# raspi_gpio_coupler.net
KiCad netlist of a schematic drawn in EAGLE
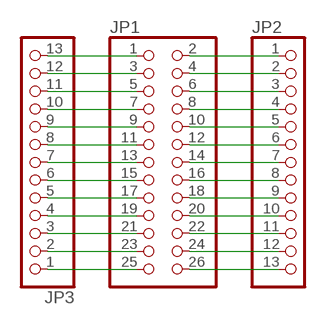
[diagram p0: schematic, sheet 1]

(export (version "E")
  (design (tool "Eeschema 10.0.6"))
  (components
    (comp (ref "JP1")
      (value "PINHD-2X13")
      (footprint "eagle-import:2X13")
      (libsource (lib "eagle-import") (part "PINHD-2X13"))
    )
    (comp (ref "JP2")
      (value "PINHD-1X13")
      (footprint "eagle-import:1X13")
      (libsource (lib "eagle-import") (part "PINHD-1X13"))
    )
    (comp (ref "JP3")
      (value "PINHD-1X13")
      (footprint "eagle-import:1X13")
      (libsource (lib "eagle-import") (part "PINHD-1X13"))
    )
  )
  (nets
    (net (code "1") (name "Net-(JP1-Pad1)") (class "Default")
      (node (ref "JP1") (pin "1") (pinfunction "1_1") (pintype "passive"))
      (node (ref "JP3") (pin "13") (pinfunction "13_13") (pintype "passive"))
    )
    (net (code "2") (name "Net-(JP1-Pad2)") (class "Default")
      (node (ref "JP1") (pin "2") (pinfunction "2_2") (pintype "passive"))
      (node (ref "JP2") (pin "1") (pinfunction "1_1") (pintype "passive"))
    )
    (net (code "3") (name "Net-(JP1-Pad3)") (class "Default")
      (node (ref "JP1") (pin "3") (pinfunction "3_3") (pintype "passive"))
      (node (ref "JP3") (pin "12") (pinfunction "12_12") (pintype "passive"))
    )
    (net (code "4") (name "Net-(JP1-Pad4)") (class "Default")
      (node (ref "JP1") (pin "4") (pinfunction "4_4") (pintype "passive"))
      (node (ref "JP2") (pin "2") (pinfunction "2_2") (pintype "passive"))
    )
    (net (code "5") (name "Net-(JP1-Pad5)") (class "Default")
      (node (ref "JP1") (pin "5") (pinfunction "5_5") (pintype "passive"))
      (node (ref "JP3") (pin "11") (pinfunction "11_11") (pintype "passive"))
    )
    (net (code "6") (name "Net-(JP1-Pad6)") (class "Default")
      (node (ref "JP1") (pin "6") (pinfunction "6_6") (pintype "passive"))
      (node (ref "JP2") (pin "3") (pinfunction "3_3") (pintype "passive"))
    )
    (net (code "7") (name "Net-(JP1-Pad7)") (class "Default")
      (node (ref "JP1") (pin "7") (pinfunction "7_7") (pintype "passive"))
      (node (ref "JP3") (pin "10") (pinfunction "10_10") (pintype "passive"))
    )
    (net (code "8") (name "Net-(JP1-Pad8)") (class "Default")
      (node (ref "JP1") (pin "8") (pinfunction "8_8") (pintype "passive"))
      (node (ref "JP2") (pin "4") (pinfunction "4_4") (pintype "passive"))
    )
    (net (code "9") (name "Net-(JP1-Pad9)") (class "Default")
      (node (ref "JP1") (pin "9") (pinfunction "9_9") (pintype "passive"))
      (node (ref "JP3") (pin "9") (pinfunction "9_9") (pintype "passive"))
    )
    (net (code "10") (name "Net-(JP1-Pad10)") (class "Default")
      (node (ref "JP1") (pin "10") (pinfunction "10_10") (pintype "passive"))
      (node (ref "JP2") (pin "5") (pinfunction "5_5") (pintype "passive"))
    )
    (net (code "11") (name "Net-(JP1-Pad11)") (class "Default")
      (node (ref "JP1") (pin "11") (pinfunction "11_11") (pintype "passive"))
      (node (ref "JP3") (pin "8") (pinfunction "8_8") (pintype "passive"))
    )
    (net (code "12") (name "Net-(JP1-Pad12)") (class "Default")
      (node (ref "JP1") (pin "12") (pinfunction "12_12") (pintype "passive"))
      (node (ref "JP2") (pin "6") (pinfunction "6_6") (pintype "passive"))
    )
    (net (code "13") (name "Net-(JP1-Pad13)") (class "Default")
      (node (ref "JP1") (pin "13") (pinfunction "13_13") (pintype "passive"))
      (node (ref "JP3") (pin "7") (pinfunction "7_7") (pintype "passive"))
    )
    (net (code "14") (name "Net-(JP1-Pad14)") (class "Default")
      (node (ref "JP1") (pin "14") (pinfunction "14_14") (pintype "passive"))
      (node (ref "JP2") (pin "7") (pinfunction "7_7") (pintype "passive"))
    )
    (net (code "15") (name "Net-(JP1-Pad15)") (class "Default")
      (node (ref "JP1") (pin "15") (pinfunction "15_15") (pintype "passive"))
      (node (ref "JP3") (pin "6") (pinfunction "6_6") (pintype "passive"))
    )
    (net (code "16") (name "Net-(JP1-Pad16)") (class "Default")
      (node (ref "JP1") (pin "16") (pinfunction "16_16") (pintype "passive"))
      (node (ref "JP2") (pin "8") (pinfunction "8_8") (pintype "passive"))
    )
    (net (code "17") (name "Net-(JP1-Pad17)") (class "Default")
      (node (ref "JP1") (pin "17") (pinfunction "17_17") (pintype "passive"))
      (node (ref "JP3") (pin "5") (pinfunction "5_5") (pintype "passive"))
    )
    (net (code "18") (name "Net-(JP1-Pad18)") (class "Default")
      (node (ref "JP1") (pin "18") (pinfunction "18_18") (pintype "passive"))
      (node (ref "JP2") (pin "9") (pinfunction "9_9") (pintype "passive"))
    )
    (net (code "19") (name "Net-(JP1-Pad19)") (class "Default")
      (node (ref "JP1") (pin "19") (pinfunction "19_19") (pintype "passive"))
      (node (ref "JP3") (pin "4") (pinfunction "4_4") (pintype "passive"))
    )
    (net (code "20") (name "Net-(JP1-Pad20)") (class "Default")
      (node (ref "JP1") (pin "20") (pinfunction "20_20") (pintype "passive"))
      (node (ref "JP2") (pin "10") (pinfunction "10_10") (pintype "passive"))
    )
    (net (code "21") (name "Net-(JP1-Pad21)") (class "Default")
      (node (ref "JP1") (pin "21") (pinfunction "21_21") (pintype "passive"))
      (node (ref "JP3") (pin "3") (pinfunction "3_3") (pintype "passive"))
    )
    (net (code "22") (name "Net-(JP1-Pad22)") (class "Default")
      (node (ref "JP1") (pin "22") (pinfunction "22_22") (pintype "passive"))
      (node (ref "JP2") (pin "11") (pinfunction "11_11") (pintype "passive"))
    )
    (net (code "23") (name "Net-(JP1-Pad23)") (class "Default")
      (node (ref "JP1") (pin "23") (pinfunction "23_23") (pintype "passive"))
      (node (ref "JP3") (pin "2") (pinfunction "2_2") (pintype "passive"))
    )
    (net (code "24") (name "Net-(JP1-Pad24)") (class "Default")
      (node (ref "JP1") (pin "24") (pinfunction "24_24") (pintype "passive"))
      (node (ref "JP2") (pin "12") (pinfunction "12_12") (pintype "passive"))
    )
    (net (code "25") (name "Net-(JP1-Pad25)") (class "Default")
      (node (ref "JP1") (pin "25") (pinfunction "25_25") (pintype "passive"))
      (node (ref "JP3") (pin "1") (pinfunction "1_1") (pintype "passive"))
    )
    (net (code "26") (name "Net-(JP1-Pad26)") (class "Default")
      (node (ref "JP1") (pin "26") (pinfunction "26_26") (pintype "passive"))
      (node (ref "JP2") (pin "13") (pinfunction "13_13") (pintype "passive"))
    )
  )
)
